# Power.net
KiCad netlist of a schematic drawn in Altium Designer
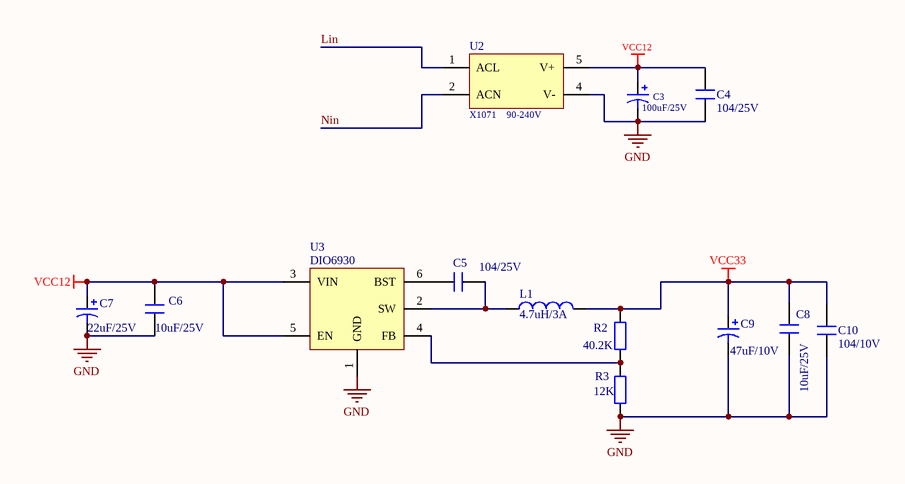
[diagram p0: Power.SchDoc]

(export (version "E")
  (design (tool "Eeschema 10.0.6"))
  (components
    (comp (ref "C3")
      (value "100uF/25V")
      (footprint "CAPPIND06")
      (description "Polarized Capacitor (Radial)")
      (fields (field (name "PUBLISHER") "Altium Limited"))
      (libsource (lib "Miscellaneous Devices") (part "Cap Pol1"))
    )
    (comp (ref "C4") (value "104/25V") (footprint "0603R") (libsource (lib "ES_Schematic") (part "CAP_1")))
    (comp (ref "C5") (value "104/25V") (footprint "0603R") (libsource (lib "ES_Schematic") (part "CAP_1")))
    (comp (ref "C6") (value "10uF/25V") (footprint "0603R") (libsource (lib "ES_Schematic") (part "CAP")))
    (comp (ref "C7")
      (value "22uF/25V")
      (footprint "0805R")
      (description "Polarized Capacitor (Radial)")
      (fields (field (name "PUBLISHER") "Altium Limited"))
      (libsource (lib "Miscellaneous Devices") (part "Cap Pol1"))
    )
    (comp (ref "C8") (value "10uF/25V") (footprint "0603R") (libsource (lib "ES_Schematic") (part "CAP")))
    (comp (ref "C9")
      (value "47uF/10V")
      (footprint "0805R")
      (description "Polarized Capacitor (Radial)")
      (fields (field (name "PUBLISHER") "Altium Limited"))
      (libsource (lib "Miscellaneous Devices") (part "Cap Pol1"))
    )
    (comp (ref "C10") (value "104/10V") (footprint "0603R") (libsource (lib "ES_Schematic") (part "CAP_1")))
    (comp (ref "L1")
      (value "4.7uH/3A")
      (footprint "贴片电感5020")
      (description "Inductor")
      (fields (field (name "PUBLISHER") "Altium Limited"))
      (libsource (lib "Miscellaneous Devices") (part "Inductor"))
    )
    (comp (ref "R2")
      (value "40.2K")
      (footprint "0603R")
      (description "Resistor")
      (fields (field (name "PUBLISHER") "Altium Limited"))
      (libsource (lib "Miscellaneous Devices") (part "Res2"))
    )
    (comp (ref "R3")
      (value "12K")
      (footprint "0603R")
      (description "Resistor")
      (fields (field (name "PUBLISHER") "Altium Limited"))
      (libsource (lib "Miscellaneous Devices") (part "Res2"))
    )
    (comp (ref "U2")
      (value "X1071    90-240V")
      (footprint "X1071")
      (libsource (lib "sangjian") (part "AD2DC_EMC"))
    )
    (comp (ref "U3")
      (value "DIO6930")
      (footprint "SOT-23-6DBV")
      (libsource (lib "ES_Schematic") (part "BL8032"))
    )
  )
  (nets
    (net (code "1") (name "/Lin") (class "Default")
      (node (ref "U2") (pin "1") (pinfunction "ACL_1") (pintype "passive"))
    )
    (net (code "2") (name "/Nin") (class "Default")
      (node (ref "U2") (pin "2") (pinfunction "ACN_2") (pintype "passive"))
    )
    (net (code "3") (name "GND") (class "Default")
      (node (ref "C10") (pin "1") (pinfunction "1_1") (pintype "passive"))
      (node (ref "C3") (pin "2") (pinfunction "2_2") (pintype "passive"))
      (node (ref "C4") (pin "1") (pinfunction "1_1") (pintype "passive"))
      (node (ref "C6") (pin "1") (pinfunction "1_1") (pintype "passive"))
      (node (ref "C7") (pin "2") (pinfunction "2_2") (pintype "passive"))
      (node (ref "C8") (pin "1") (pinfunction "1_1") (pintype "passive"))
      (node (ref "C9") (pin "2") (pinfunction "2_2") (pintype "passive"))
      (node (ref "R3") (pin "2") (pinfunction "2_2") (pintype "passive"))
      (node (ref "U2") (pin "4") (pinfunction "V-_4") (pintype "passive"))
      (node (ref "U3") (pin "1") (pinfunction "GND_1") (pintype "passive"))
    )
    (net (code "4") (name "Net-(U3-BST)") (class "Default")
      (node (ref "C5") (pin "2") (pinfunction "2_2") (pintype "passive"))
      (node (ref "U3") (pin "6") (pinfunction "BST_6") (pintype "passive"))
    )
    (net (code "5") (name "Net-(U3-FB)") (class "Default")
      (node (ref "R2") (pin "2") (pinfunction "2_2") (pintype "passive"))
      (node (ref "R3") (pin "1") (pinfunction "1_1") (pintype "passive"))
      (node (ref "U3") (pin "4") (pinfunction "FB_4") (pintype "passive"))
    )
    (net (code "6") (name "Net-(U3-SW)") (class "Default")
      (node (ref "C5") (pin "1") (pinfunction "1_1") (pintype "passive"))
      (node (ref "L1") (pin "1") (pinfunction "1_1") (pintype "passive"))
      (node (ref "U3") (pin "2") (pinfunction "SW_2") (pintype "passive"))
    )
    (net (code "7") (name "VCC12") (class "Default")
      (node (ref "C3") (pin "1") (pinfunction "1_1") (pintype "passive"))
      (node (ref "C4") (pin "2") (pinfunction "2_2") (pintype "passive"))
      (node (ref "C6") (pin "2") (pinfunction "2_2") (pintype "passive"))
      (node (ref "C7") (pin "1") (pinfunction "1_1") (pintype "passive"))
      (node (ref "U2") (pin "5") (pinfunction "V+_5") (pintype "passive"))
      (node (ref "U3") (pin "3") (pinfunction "VIN_3") (pintype "passive"))
      (node (ref "U3") (pin "5") (pinfunction "EN_5") (pintype "passive"))
    )
    (net (code "8") (name "VCC33") (class "Default")
      (node (ref "C10") (pin "2") (pinfunction "2_2") (pintype "passive"))
      (node (ref "C8") (pin "2") (pinfunction "2_2") (pintype "passive"))
      (node (ref "C9") (pin "1") (pinfunction "1_1") (pintype "passive"))
      (node (ref "L1") (pin "2") (pinfunction "2_2") (pintype "passive"))
      (node (ref "R2") (pin "1") (pinfunction "1_1") (pintype "passive"))
    )
  )
)
